# R-Divider-Breakout.net
KiCad netlist of a schematic drawn in EAGLE
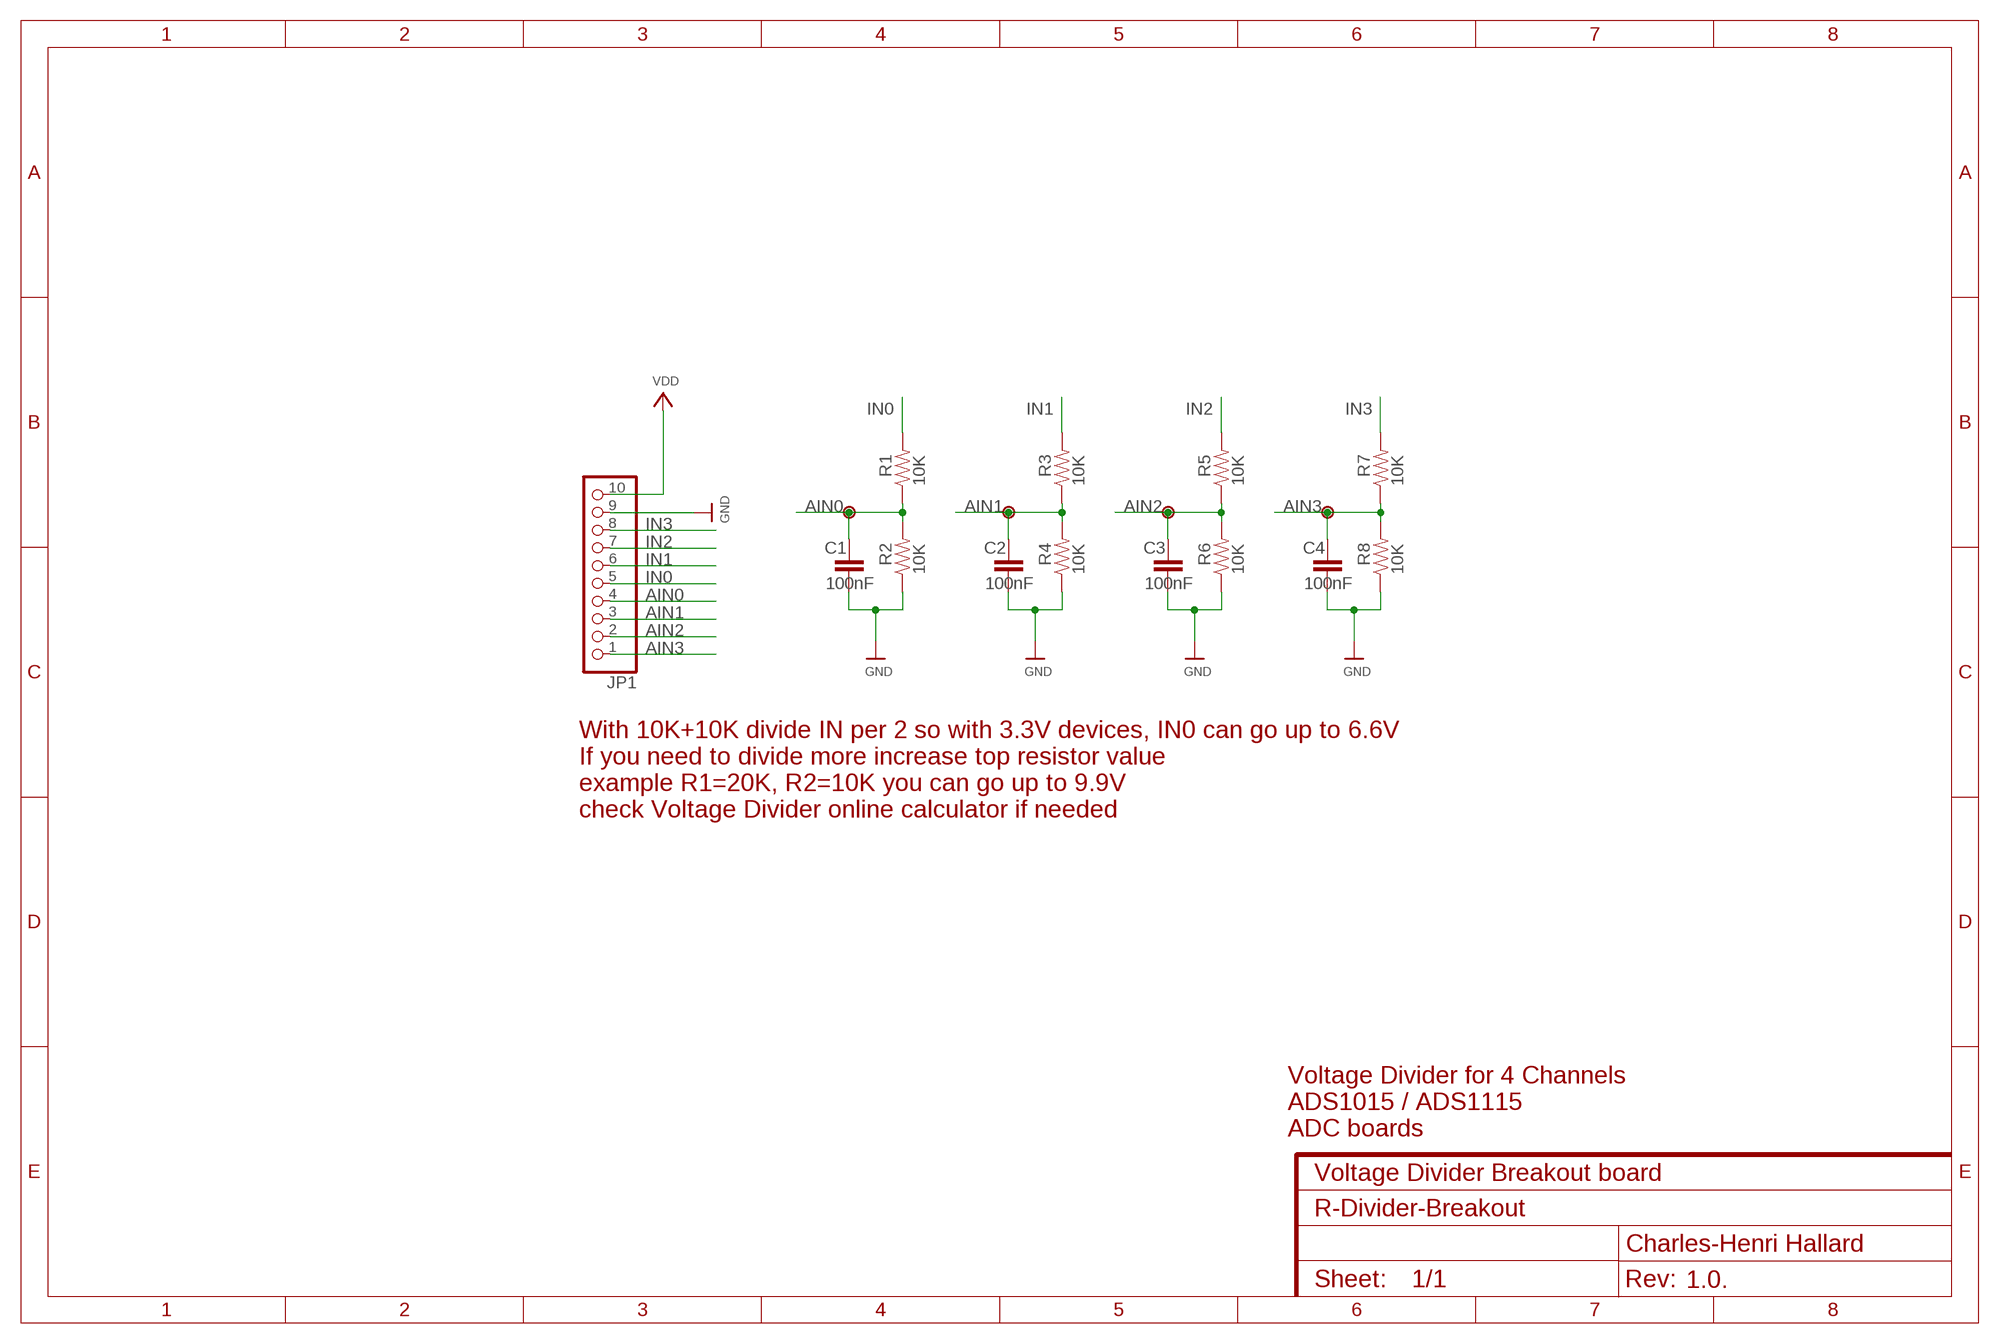
[diagram p0: schematic, sheet 1]

(export (version "E")
  (design (tool "Eeschema 10.0.6"))
  (components
    (comp (ref "C1")
      (value "100nF")
      (footprint "eagle-import:0805-CAP")
      (libsource (lib "eagle-import") (part "CAP0805-CAP"))
    )
    (comp (ref "C2")
      (value "100nF")
      (footprint "eagle-import:0805-CAP")
      (libsource (lib "eagle-import") (part "CAP0805-CAP"))
    )
    (comp (ref "C3")
      (value "100nF")
      (footprint "eagle-import:0805-CAP")
      (libsource (lib "eagle-import") (part "CAP0805-CAP"))
    )
    (comp (ref "C4")
      (value "100nF")
      (footprint "eagle-import:0805-CAP")
      (libsource (lib "eagle-import") (part "CAP0805-CAP"))
    )
    (comp (ref "JP1")
      (value "HEADER-1X1070MIL")
      (footprint "eagle-import:1X10_ROUND70")
      (libsource (lib "eagle-import") (part "HEADER-1X1070MIL"))
    )
    (comp (ref "P1")
      (value "PADSMALL")
      (footprint "eagle-import:PAD-SMALL")
      (libsource (lib "eagle-import") (part "PADSMALL"))
    )
    (comp (ref "P2")
      (value "PADSMALL")
      (footprint "eagle-import:PAD-SMALL")
      (libsource (lib "eagle-import") (part "PADSMALL"))
    )
    (comp (ref "P3")
      (value "PADSMALL")
      (footprint "eagle-import:PAD-SMALL")
      (libsource (lib "eagle-import") (part "PADSMALL"))
    )
    (comp (ref "P4")
      (value "PADSMALL")
      (footprint "eagle-import:PAD-SMALL")
      (libsource (lib "eagle-import") (part "PADSMALL"))
    )
    (comp (ref "R1")
      (value "10K")
      (footprint "eagle-import:0805-RES")
      (libsource (lib "eagle-import") (part "RESISTOR0805-RES"))
    )
    (comp (ref "R2")
      (value "10K")
      (footprint "eagle-import:0805-RES")
      (libsource (lib "eagle-import") (part "RESISTOR0805-RES"))
    )
    (comp (ref "R3")
      (value "10K")
      (footprint "eagle-import:0805-RES")
      (libsource (lib "eagle-import") (part "RESISTOR0805-RES"))
    )
    (comp (ref "R4")
      (value "10K")
      (footprint "eagle-import:0805-RES")
      (libsource (lib "eagle-import") (part "RESISTOR0805-RES"))
    )
    (comp (ref "R5")
      (value "10K")
      (footprint "eagle-import:0805-RES")
      (libsource (lib "eagle-import") (part "RESISTOR0805-RES"))
    )
    (comp (ref "R6")
      (value "10K")
      (footprint "eagle-import:0805-RES")
      (libsource (lib "eagle-import") (part "RESISTOR0805-RES"))
    )
    (comp (ref "R7")
      (value "10K")
      (footprint "eagle-import:0805-RES")
      (libsource (lib "eagle-import") (part "RESISTOR0805-RES"))
    )
    (comp (ref "R8")
      (value "10K")
      (footprint "eagle-import:0805-RES")
      (libsource (lib "eagle-import") (part "RESISTOR0805-RES"))
    )
  )
  (nets
    (net (code "1") (name "/AIN0") (class "Default")
      (node (ref "C1") (pin "1") (pinfunction "1_1") (pintype "passive"))
      (node (ref "JP1") (pin "4") (pinfunction "4_4") (pintype "passive"))
      (node (ref "P1") (pin "1") (pinfunction "1_1") (pintype "bidirectional"))
      (node (ref "R1") (pin "1") (pinfunction "1_1") (pintype "passive"))
      (node (ref "R2") (pin "2") (pinfunction "2_2") (pintype "passive"))
    )
    (net (code "2") (name "/AIN1") (class "Default")
      (node (ref "C2") (pin "1") (pinfunction "1_1") (pintype "passive"))
      (node (ref "JP1") (pin "3") (pinfunction "3_3") (pintype "passive"))
      (node (ref "P2") (pin "1") (pinfunction "1_1") (pintype "bidirectional"))
      (node (ref "R3") (pin "1") (pinfunction "1_1") (pintype "passive"))
      (node (ref "R4") (pin "2") (pinfunction "2_2") (pintype "passive"))
    )
    (net (code "3") (name "/AIN2") (class "Default")
      (node (ref "C3") (pin "1") (pinfunction "1_1") (pintype "passive"))
      (node (ref "JP1") (pin "2") (pinfunction "2_2") (pintype "passive"))
      (node (ref "P3") (pin "1") (pinfunction "1_1") (pintype "bidirectional"))
      (node (ref "R5") (pin "1") (pinfunction "1_1") (pintype "passive"))
      (node (ref "R6") (pin "2") (pinfunction "2_2") (pintype "passive"))
    )
    (net (code "4") (name "/AIN3") (class "Default")
      (node (ref "C4") (pin "1") (pinfunction "1_1") (pintype "passive"))
      (node (ref "JP1") (pin "1") (pinfunction "1_1") (pintype "passive"))
      (node (ref "P4") (pin "1") (pinfunction "1_1") (pintype "bidirectional"))
      (node (ref "R7") (pin "1") (pinfunction "1_1") (pintype "passive"))
      (node (ref "R8") (pin "2") (pinfunction "2_2") (pintype "passive"))
    )
    (net (code "5") (name "/IN0") (class "Default")
      (node (ref "JP1") (pin "5") (pinfunction "5_5") (pintype "passive"))
      (node (ref "R1") (pin "2") (pinfunction "2_2") (pintype "passive"))
    )
    (net (code "6") (name "/IN1") (class "Default")
      (node (ref "JP1") (pin "6") (pinfunction "6_6") (pintype "passive"))
      (node (ref "R3") (pin "2") (pinfunction "2_2") (pintype "passive"))
    )
    (net (code "7") (name "/IN2") (class "Default")
      (node (ref "JP1") (pin "7") (pinfunction "7_7") (pintype "passive"))
      (node (ref "R5") (pin "2") (pinfunction "2_2") (pintype "passive"))
    )
    (net (code "8") (name "/IN3") (class "Default")
      (node (ref "JP1") (pin "8") (pinfunction "8_8") (pintype "passive"))
      (node (ref "R7") (pin "2") (pinfunction "2_2") (pintype "passive"))
    )
    (net (code "9") (name "GND") (class "Default")
      (node (ref "C1") (pin "2") (pinfunction "2_2") (pintype "passive"))
      (node (ref "C2") (pin "2") (pinfunction "2_2") (pintype "passive"))
      (node (ref "C3") (pin "2") (pinfunction "2_2") (pintype "passive"))
      (node (ref "C4") (pin "2") (pinfunction "2_2") (pintype "passive"))
      (node (ref "JP1") (pin "9") (pinfunction "9_9") (pintype "passive"))
      (node (ref "R2") (pin "1") (pinfunction "1_1") (pintype "passive"))
      (node (ref "R4") (pin "1") (pinfunction "1_1") (pintype "passive"))
      (node (ref "R6") (pin "1") (pinfunction "1_1") (pintype "passive"))
      (node (ref "R8") (pin "1") (pinfunction "1_1") (pintype "passive"))
    )
    (net (code "10") (name "VDD") (class "Default")
      (node (ref "JP1") (pin "10") (pinfunction "10_10") (pintype "passive"))
    )
  )
)
